# pax_counter.net
KiCad netlist of a schematic drawn in EAGLE
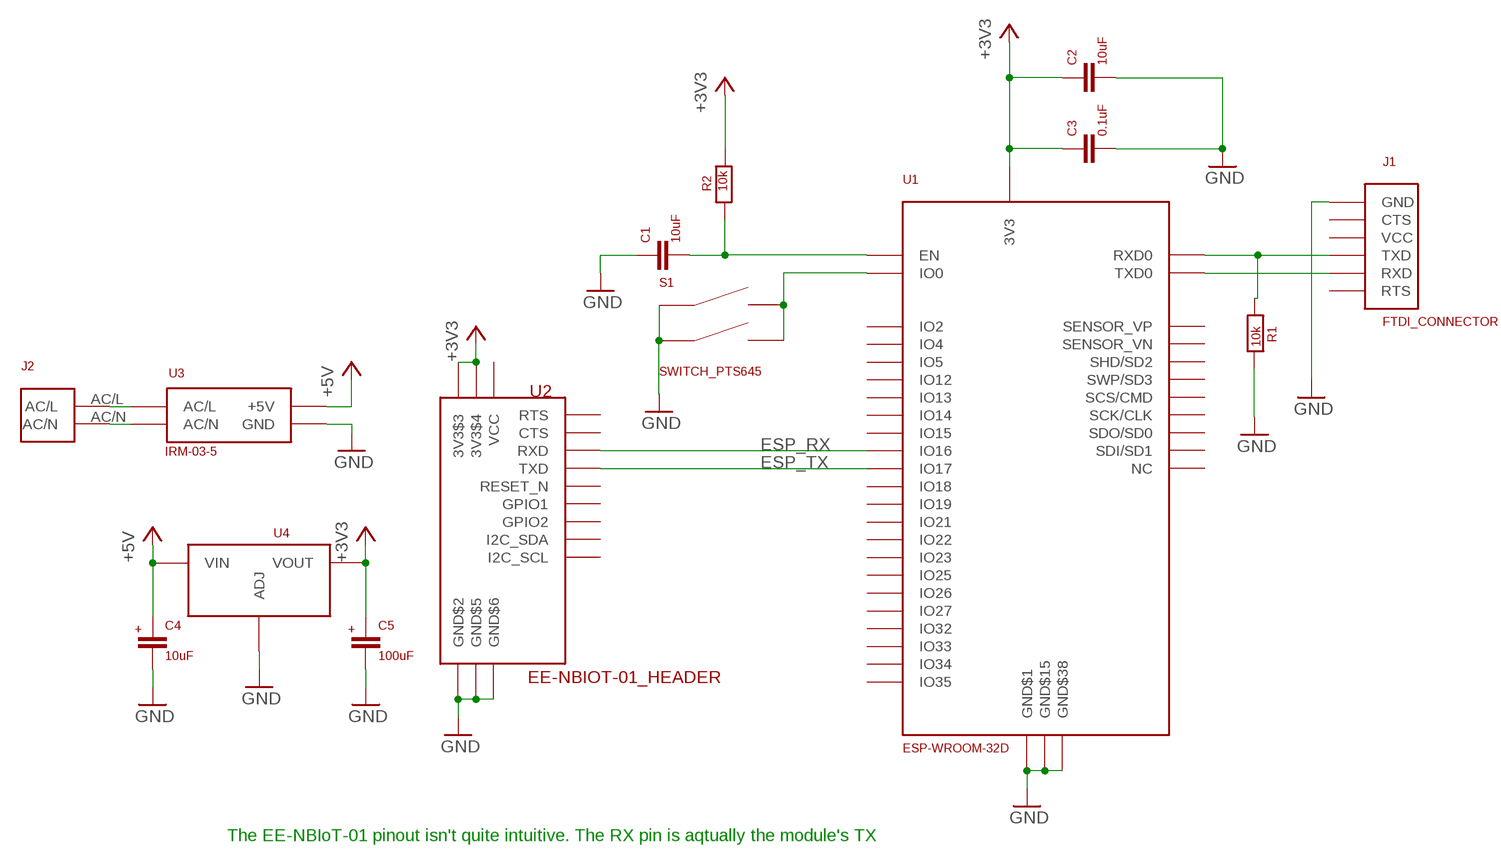
[diagram p0: schematic, sheet 1]

(export (version "E")
  (design (tool "Eeschema 10.0.6"))
  (components
    (comp (ref "C1")
      (value "10uF")
      (footprint "eagle-import:CAP_0402")
      (libsource (lib "eagle-import") (part "CAPACITOR0402"))
    )
    (comp (ref "C2")
      (value "10uF")
      (footprint "eagle-import:CAP_0402")
      (libsource (lib "eagle-import") (part "CAPACITOR0402"))
    )
    (comp (ref "C3")
      (value "0.1uF")
      (footprint "eagle-import:CAP_0402")
      (libsource (lib "eagle-import") (part "CAPACITOR0402"))
    )
    (comp (ref "C4")
      (value "10uF")
      (footprint "eagle-import:TANTALUM_CAP_1206")
      (libsource (lib "eagle-import") (part "TANTALUM_CAPACITOR"))
    )
    (comp (ref "C5")
      (value "100uF")
      (footprint "eagle-import:TANTALUM_CAP_1206")
      (libsource (lib "eagle-import") (part "TANTALUM_CAPACITOR"))
    )
    (comp (ref "J1")
      (value "FTDI_CONNECTOR")
      (footprint "eagle-import:FTDI_CONNECTOR")
      (libsource (lib "eagle-import") (part "FTDI_CONNECTOR"))
    )
    (comp (ref "J2")
      (value "240VAC_SOLDER_CONNECTOR")
      (footprint "eagle-import:240VAC_SOLDER_CONNECTOR")
      (libsource (lib "eagle-import") (part "240VAC_SOLDER_CONNECTOR"))
    )
    (comp (ref "R1")
      (value "10k")
      (footprint "eagle-import:RES_0402")
      (libsource (lib "eagle-import") (part "RESISTOR"))
    )
    (comp (ref "R2")
      (value "10k")
      (footprint "eagle-import:RES_0402")
      (libsource (lib "eagle-import") (part "RESISTOR"))
    )
    (comp (ref "S1")
      (value "SWITCH_PTS645")
      (footprint "eagle-import:SWITCH_PTS645_EE_NBIOT_01")
      (libsource (lib "eagle-import") (part "SWITCH_PTS645"))
    )
    (comp (ref "U1")
      (value "ESP-WROOM-32D")
      (footprint "eagle-import:ESP_WROOM_32D")
      (libsource (lib "eagle-import") (part "ESP-WROOM-32D"))
    )
    (comp (ref "U2")
      (value "EE-NBIOT-01_HEADER")
      (footprint "eagle-import:EE-NBIOT-01_HEADER")
      (libsource (lib "eagle-import") (part "EE-NBIOT-01_HEADER"))
    )
    (comp (ref "U3")
      (value "IRM-03-5")
      (footprint "eagle-import:IRM-03-5")
      (libsource (lib "eagle-import") (part "IRM-03-5"))
    )
    (comp (ref "U4")
      (value "LM1117")
      (footprint "eagle-import:SOT-223")
      (libsource (lib "eagle-import") (part "LM1117"))
    )
  )
  (nets
    (net (code "1") (name "+3V3") (class "Default")
      (node (ref "C2") (pin "P$1") (pinfunction "1_P$1") (pintype "passive"))
      (node (ref "C3") (pin "P$1") (pinfunction "1_P$1") (pintype "passive"))
      (node (ref "C5") (pin "V+") (pinfunction "+_V+") (pintype "passive"))
      (node (ref "R2") (pin "P$2") (pinfunction "P$2_P$2") (pintype "bidirectional"))
      (node (ref "U1") (pin "2") (pinfunction "3V3_2") (pintype "bidirectional"))
      (node (ref "U2") (pin "3V3$3") (pinfunction "3V3$3_3V3$3") (pintype "bidirectional"))
      (node (ref "U2") (pin "3V3$4") (pinfunction "3V3$4_3V3$4") (pintype "bidirectional"))
      (node (ref "U4") (pin "P$2") (pinfunction "VOUT_P$2") (pintype "bidirectional"))
      (node (ref "U4") (pin "VOUT$1") (pinfunction "VOUT_VOUT$1") (pintype "bidirectional"))
    )
    (net (code "2") (name "+5V") (class "Default")
      (node (ref "C4") (pin "V+") (pinfunction "+_V+") (pintype "passive"))
      (node (ref "U3") (pin "+5V") (pinfunction "+5V_+5V") (pintype "bidirectional"))
      (node (ref "U4") (pin "VIN") (pinfunction "VIN_VIN") (pintype "bidirectional"))
    )
    (net (code "3") (name "/ESP_RX") (class "Default")
      (node (ref "U1") (pin "27") (pinfunction "IO16_27") (pintype "bidirectional"))
      (node (ref "U2") (pin "RXD") (pinfunction "RXD_RXD") (pintype "bidirectional"))
    )
    (net (code "4") (name "/ESP_TX") (class "Default")
      (node (ref "U1") (pin "28") (pinfunction "IO17_28") (pintype "bidirectional"))
      (node (ref "U2") (pin "TXD") (pinfunction "TXD_TXD") (pintype "bidirectional"))
    )
    (net (code "5") (name "GND") (class "Default")
      (node (ref "C1") (pin "P$1") (pinfunction "1_P$1") (pintype "passive"))
      (node (ref "C2") (pin "P$2") (pinfunction "2_P$2") (pintype "passive"))
      (node (ref "C3") (pin "P$2") (pinfunction "2_P$2") (pintype "passive"))
      (node (ref "C4") (pin "GND") (pinfunction "-_GND") (pintype "passive"))
      (node (ref "C5") (pin "GND") (pinfunction "-_GND") (pintype "passive"))
      (node (ref "J1") (pin "GND") (pinfunction "GND_GND") (pintype "bidirectional"))
      (node (ref "R1") (pin "P$2") (pinfunction "P$2_P$2") (pintype "bidirectional"))
      (node (ref "S1") (pin "A1") (pinfunction "A1_A1") (pintype "bidirectional"))
      (node (ref "S1") (pin "A2") (pinfunction "A2_A2") (pintype "bidirectional"))
      (node (ref "U1") (pin "1") (pinfunction "GND$1_1") (pintype "bidirectional"))
      (node (ref "U1") (pin "15") (pinfunction "GND$15_15") (pintype "bidirectional"))
      (node (ref "U1") (pin "38") (pinfunction "GND$38_38") (pintype "bidirectional"))
      (node (ref "U1") (pin "GND$39") (pinfunction "GND$38_GND$39") (pintype "bidirectional"))
      (node (ref "U1") (pin "GND$40") (pinfunction "GND$38_GND$40") (pintype "bidirectional"))
      (node (ref "U1") (pin "GND$41") (pinfunction "GND$38_GND$41") (pintype "bidirectional"))
      (node (ref "U1") (pin "GND$42") (pinfunction "GND$38_GND$42") (pintype "bidirectional"))
      (node (ref "U1") (pin "GND$43") (pinfunction "GND$38_GND$43") (pintype "bidirectional"))
      (node (ref "U1") (pin "GND$44") (pinfunction "GND$38_GND$44") (pintype "bidirectional"))
      (node (ref "U1") (pin "GND$45") (pinfunction "GND$38_GND$45") (pintype "bidirectional"))
      (node (ref "U1") (pin "GND$46") (pinfunction "GND$38_GND$46") (pintype "bidirectional"))
      (node (ref "U1") (pin "GND$47") (pinfunction "GND$38_GND$47") (pintype "bidirectional"))
      (node (ref "U2") (pin "GND$2") (pinfunction "GND$2_GND$2") (pintype "bidirectional"))
      (node (ref "U2") (pin "GND$5") (pinfunction "GND$5_GND$5") (pintype "bidirectional"))
      (node (ref "U2") (pin "GND$6") (pinfunction "GND$6_GND$6") (pintype "bidirectional"))
      (node (ref "U3") (pin "GND") (pinfunction "GND_GND") (pintype "bidirectional"))
      (node (ref "U4") (pin "GND") (pinfunction "ADJ_GND") (pintype "bidirectional"))
    )
    (net (code "6") (name "Net-(C1-2)") (class "Default")
      (node (ref "C1") (pin "P$2") (pinfunction "2_P$2") (pintype "passive"))
      (node (ref "R2") (pin "P$1") (pinfunction "P$1_P$1") (pintype "bidirectional"))
      (node (ref "U1") (pin "3") (pinfunction "EN_3") (pintype "bidirectional"))
    )
    (net (code "7") (name "Net-(J2-PadAC{slash}L)") (class "Default")
      (node (ref "J2") (pin "AC/L") (pinfunction "AC/L_AC/L") (pintype "bidirectional"))
      (node (ref "U3") (pin "AC/L") (pinfunction "AC/L_AC/L") (pintype "bidirectional"))
    )
    (net (code "8") (name "Net-(J2-PadAC{slash}N)") (class "Default")
      (node (ref "J2") (pin "AC/N") (pinfunction "AC/N_AC/N") (pintype "bidirectional"))
      (node (ref "U3") (pin "AC/N") (pinfunction "AC/N_AC/N") (pintype "bidirectional"))
    )
    (net (code "9") (name "Net-(U1-IO0)") (class "Default")
      (node (ref "S1") (pin "B1") (pinfunction "B1_B1") (pintype "bidirectional"))
      (node (ref "S1") (pin "B2") (pinfunction "B2_B2") (pintype "bidirectional"))
      (node (ref "U1") (pin "25") (pinfunction "IO0_25") (pintype "bidirectional"))
    )
    (net (code "10") (name "Net-(U1-RXD0)") (class "Default")
      (node (ref "J1") (pin "TXD") (pinfunction "TXD_TXD") (pintype "bidirectional"))
      (node (ref "R1") (pin "P$1") (pinfunction "P$1_P$1") (pintype "bidirectional"))
      (node (ref "U1") (pin "34") (pinfunction "RXD0_34") (pintype "bidirectional"))
    )
    (net (code "11") (name "Net-(U1-TXD0)") (class "Default")
      (node (ref "J1") (pin "RXD") (pinfunction "RXD_RXD") (pintype "bidirectional"))
      (node (ref "U1") (pin "35") (pinfunction "TXD0_35") (pintype "bidirectional"))
    )
    (net (code "12") (name "unconnected-(J1-PadCTS)") (class "Default")
      (node (ref "J1") (pin "CTS") (pinfunction "CTS_CTS") (pintype "bidirectional"))
    )
    (net (code "13") (name "unconnected-(J1-PadRTS)") (class "Default")
      (node (ref "J1") (pin "RTS") (pinfunction "RTS_RTS") (pintype "bidirectional"))
    )
    (net (code "14") (name "unconnected-(J1-PadVCC)") (class "Default")
      (node (ref "J1") (pin "VCC") (pinfunction "VCC_VCC") (pintype "bidirectional"))
    )
    (net (code "15") (name "unconnected-(U1-IO2-Pad24)") (class "Default")
      (node (ref "U1") (pin "24") (pinfunction "IO2_24") (pintype "bidirectional"))
    )
    (net (code "16") (name "unconnected-(U1-IO4-Pad26)") (class "Default")
      (node (ref "U1") (pin "26") (pinfunction "IO4_26") (pintype "bidirectional"))
    )
    (net (code "17") (name "unconnected-(U1-IO5-Pad29)") (class "Default")
      (node (ref "U1") (pin "29") (pinfunction "IO5_29") (pintype "bidirectional"))
    )
    (net (code "18") (name "unconnected-(U1-IO12-Pad14)") (class "Default")
      (node (ref "U1") (pin "14") (pinfunction "IO12_14") (pintype "bidirectional"))
    )
    (net (code "19") (name "unconnected-(U1-IO13-Pad16)") (class "Default")
      (node (ref "U1") (pin "16") (pinfunction "IO13_16") (pintype "bidirectional"))
    )
    (net (code "20") (name "unconnected-(U1-IO14-Pad13)") (class "Default")
      (node (ref "U1") (pin "13") (pinfunction "IO14_13") (pintype "bidirectional"))
    )
    (net (code "21") (name "unconnected-(U1-IO15-Pad23)") (class "Default")
      (node (ref "U1") (pin "23") (pinfunction "IO15_23") (pintype "bidirectional"))
    )
    (net (code "22") (name "unconnected-(U1-IO18-Pad30)") (class "Default")
      (node (ref "U1") (pin "30") (pinfunction "IO18_30") (pintype "bidirectional"))
    )
    (net (code "23") (name "unconnected-(U1-IO19-Pad31)") (class "Default")
      (node (ref "U1") (pin "31") (pinfunction "IO19_31") (pintype "bidirectional"))
    )
    (net (code "24") (name "unconnected-(U1-IO21-Pad33)") (class "Default")
      (node (ref "U1") (pin "33") (pinfunction "IO21_33") (pintype "bidirectional"))
    )
    (net (code "25") (name "unconnected-(U1-IO22-Pad36)") (class "Default")
      (node (ref "U1") (pin "36") (pinfunction "IO22_36") (pintype "bidirectional"))
    )
    (net (code "26") (name "unconnected-(U1-IO23-Pad37)") (class "Default")
      (node (ref "U1") (pin "37") (pinfunction "IO23_37") (pintype "bidirectional"))
    )
    (net (code "27") (name "unconnected-(U1-IO25-Pad10)") (class "Default")
      (node (ref "U1") (pin "10") (pinfunction "IO25_10") (pintype "bidirectional"))
    )
    (net (code "28") (name "unconnected-(U1-IO26-Pad11)") (class "Default")
      (node (ref "U1") (pin "11") (pinfunction "IO26_11") (pintype "bidirectional"))
    )
    (net (code "29") (name "unconnected-(U1-IO27-Pad12)") (class "Default")
      (node (ref "U1") (pin "12") (pinfunction "IO27_12") (pintype "bidirectional"))
    )
    (net (code "30") (name "unconnected-(U1-IO32-Pad8)") (class "Default")
      (node (ref "U1") (pin "8") (pinfunction "IO32_8") (pintype "bidirectional"))
    )
    (net (code "31") (name "unconnected-(U1-IO33-Pad9)") (class "Default")
      (node (ref "U1") (pin "9") (pinfunction "IO33_9") (pintype "bidirectional"))
    )
    (net (code "32") (name "unconnected-(U1-IO34-Pad6)") (class "Default")
      (node (ref "U1") (pin "6") (pinfunction "IO34_6") (pintype "bidirectional"))
    )
    (net (code "33") (name "unconnected-(U1-IO35-Pad7)") (class "Default")
      (node (ref "U1") (pin "7") (pinfunction "IO35_7") (pintype "bidirectional"))
    )
    (net (code "34") (name "unconnected-(U1-NC-Pad32)") (class "Default")
      (node (ref "U1") (pin "32") (pinfunction "NC_32") (pintype "bidirectional"))
    )
    (net (code "35") (name "unconnected-(U1-SCK{slash}CLK-Pad20)") (class "Default")
      (node (ref "U1") (pin "20") (pinfunction "SCK/CLK_20") (pintype "bidirectional"))
    )
    (net (code "36") (name "unconnected-(U1-SCS{slash}CMD-Pad19)") (class "Default")
      (node (ref "U1") (pin "19") (pinfunction "SCS/CMD_19") (pintype "bidirectional"))
    )
    (net (code "37") (name "unconnected-(U1-SDI{slash}SD1-Pad22)") (class "Default")
      (node (ref "U1") (pin "22") (pinfunction "SDI/SD1_22") (pintype "bidirectional"))
    )
    (net (code "38") (name "unconnected-(U1-SDO{slash}SD0-Pad21)") (class "Default")
      (node (ref "U1") (pin "21") (pinfunction "SDO/SD0_21") (pintype "bidirectional"))
    )
    (net (code "39") (name "unconnected-(U1-SENSOR_VN-Pad5)") (class "Default")
      (node (ref "U1") (pin "5") (pinfunction "SENSOR_VN_5") (pintype "bidirectional"))
    )
    (net (code "40") (name "unconnected-(U1-SENSOR_VP-Pad4)") (class "Default")
      (node (ref "U1") (pin "4") (pinfunction "SENSOR_VP_4") (pintype "bidirectional"))
    )
    (net (code "41") (name "unconnected-(U1-SHD{slash}SD2-Pad17)") (class "Default")
      (node (ref "U1") (pin "17") (pinfunction "SHD/SD2_17") (pintype "bidirectional"))
    )
    (net (code "42") (name "unconnected-(U1-SWP{slash}SD3-Pad18)") (class "Default")
      (node (ref "U1") (pin "18") (pinfunction "SWP/SD3_18") (pintype "bidirectional"))
    )
    (net (code "43") (name "unconnected-(U2-PadCTS)") (class "Default")
      (node (ref "U2") (pin "CTS") (pinfunction "CTS_CTS") (pintype "bidirectional"))
    )
    (net (code "44") (name "unconnected-(U2-PadGPIO1)") (class "Default")
      (node (ref "U2") (pin "GPIO1") (pinfunction "GPIO1_GPIO1") (pintype "bidirectional"))
    )
    (net (code "45") (name "unconnected-(U2-PadGPIO2)") (class "Default")
      (node (ref "U2") (pin "GPIO2") (pinfunction "GPIO2_GPIO2") (pintype "bidirectional"))
    )
    (net (code "46") (name "unconnected-(U2-PadI2C_SCL)") (class "Default")
      (node (ref "U2") (pin "I2C_SCL") (pinfunction "I2C_SCL_I2C_SCL") (pintype "bidirectional"))
    )
    (net (code "47") (name "unconnected-(U2-PadI2C_SDA)") (class "Default")
      (node (ref "U2") (pin "I2C_SDA") (pinfunction "I2C_SDA_I2C_SDA") (pintype "bidirectional"))
    )
    (net (code "48") (name "unconnected-(U2-PadRESET_N)") (class "Default")
      (node (ref "U2") (pin "RESET_N") (pinfunction "RESET_N_RESET_N") (pintype "bidirectional"))
    )
    (net (code "49") (name "unconnected-(U2-PadRTS)") (class "Default")
      (node (ref "U2") (pin "RTS") (pinfunction "RTS_RTS") (pintype "bidirectional"))
    )
    (net (code "50") (name "unconnected-(U2-PadVCC)") (class "Default")
      (node (ref "U2") (pin "VCC") (pinfunction "VCC_VCC") (pintype "bidirectional"))
    )
  )
)
